# TPSM84824MOL.net
KiCad netlist of a schematic drawn in Altium Designer
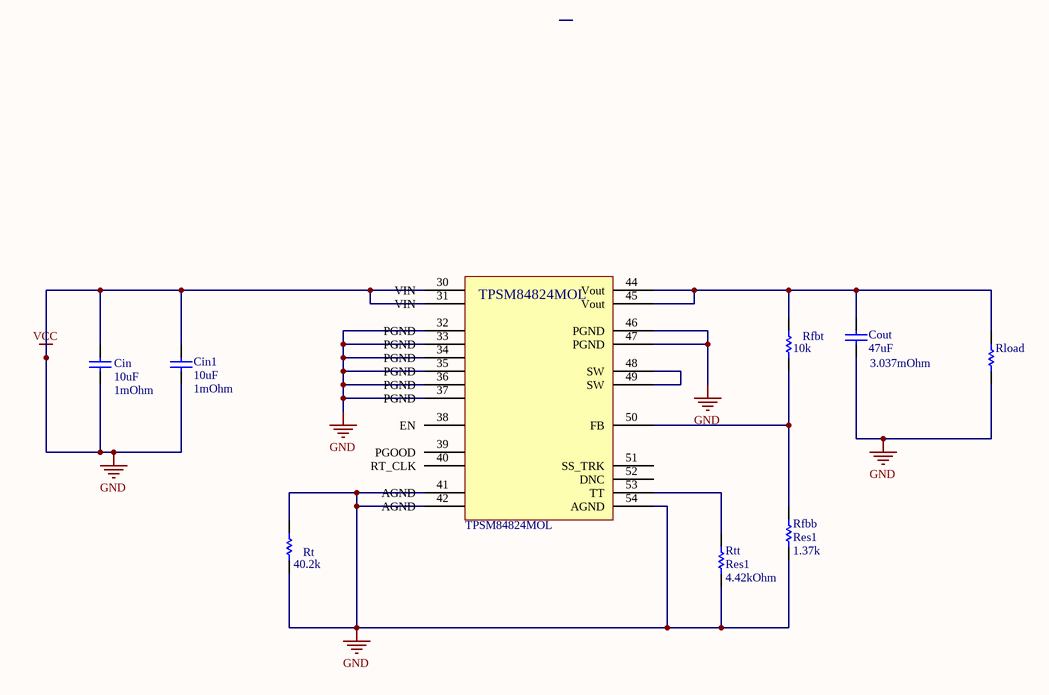
[diagram p0: TPSM84824MOL.SchDoc]

(export (version "E")
  (design (tool "Eeschema 10.0.6"))
  (components
    (comp (ref "Cin")
      (value "10uF")
      (footprint "RAD-0.3")
      (description "Capacitor")
      (fields
        (field (name "ALTIUM_UNNAMED_1") "1mOhm")
        (field (name "Comment") "Cap")
        (field (name "PUBLISHER") "Altium Limited")
      )
      (libsource (lib "Miscellaneous Devices") (part "Cap"))
    )
    (comp (ref "Cin1")
      (value "10uF")
      (footprint "RAD-0.3")
      (description "Capacitor")
      (fields
        (field (name "ALTIUM_UNNAMED_1") "1mOhm")
        (field (name "Comment") "Cap")
        (field (name "PUBLISHER") "Altium Limited")
      )
      (libsource (lib "Miscellaneous Devices") (part "Cap"))
    )
    (comp (ref "Cout")
      (value "47uF")
      (footprint "RAD-0.3")
      (description "Capacitor")
      (fields
        (field (name "RES") "3.037mOhm")
        (field (name "Comment") "Cap")
        (field (name "PUBLISHER") "Altium Limited")
      )
      (libsource (lib "Miscellaneous Devices") (part "Cap"))
    )
    (comp (ref "Rfbb")
      (value "Res1")
      (footprint "AXIAL-0.3")
      (description "Resistor")
      (fields (field (name "ALTIUM_VALUE") "1.37k") (field (name "PUBLISHER") "Altium Limited"))
      (libsource (lib "Miscellaneous Devices") (part "Res1"))
    )
    (comp (ref "Rfbt")
      (value "10k")
      (footprint "AXIAL-0.3")
      (description "Resistor")
      (fields (field (name "Comment") "Res1") (field (name "PUBLISHER") "Altium Limited"))
      (libsource (lib "Miscellaneous Devices") (part "Res1"))
    )
    (comp (ref "Rload")
      (value "Res1")
      (footprint "AXIAL-0.3")
      (description "Resistor")
      (fields (field (name "PUBLISHER") "Altium Limited"))
      (libsource (lib "Miscellaneous Devices") (part "Res1"))
    )
    (comp (ref "Rt")
      (value "40.2k")
      (footprint "AXIAL-0.3")
      (description "Resistor")
      (fields (field (name "Comment") "Res1") (field (name "PUBLISHER") "Altium Limited"))
      (libsource (lib "Miscellaneous Devices") (part "Res1"))
    )
    (comp (ref "Rtt")
      (value "Res1")
      (footprint "AXIAL-0.3")
      (description "Resistor")
      (fields (field (name "ALTIUM_VALUE") "4.42kOhm") (field (name "PUBLISHER") "Altium Limited"))
      (libsource (lib "Miscellaneous Devices") (part "Res1"))
    )
    (comp (ref "TPSM84824MOL") (value "TPSM84824MOL") (libsource (lib "TPSM84824MOL") (part "TPSM84824MOL")))
  )
  (nets
    (net (code "1") (name "GND") (class "Default")
      (node (ref "Cin") (pin "1") (pinfunction "1_1") (pintype "passive"))
      (node (ref "Cin") (pin "2") (pinfunction "2_2") (pintype "passive"))
      (node (ref "Cin1") (pin "1") (pinfunction "1_1") (pintype "passive"))
      (node (ref "Cin1") (pin "2") (pinfunction "2_2") (pintype "passive"))
      (node (ref "Cout") (pin "1") (pinfunction "1_1") (pintype "passive"))
      (node (ref "Rfbb") (pin "1") (pinfunction "1_1") (pintype "passive"))
      (node (ref "Rload") (pin "1") (pinfunction "1_1") (pintype "passive"))
      (node (ref "Rt") (pin "1") (pinfunction "1_1") (pintype "passive"))
      (node (ref "Rt") (pin "2") (pinfunction "2_2") (pintype "passive"))
      (node (ref "Rtt") (pin "1") (pinfunction "1_1") (pintype "passive"))
      (node (ref "TPSM84824MOL") (pin "46") (pinfunction "PGND_46") (pintype "passive"))
      (node (ref "TPSM84824MOL") (pin "47") (pinfunction "PGND_47") (pintype "passive"))
      (node (ref "TPSM84824MOL") (pin "54") (pinfunction "AGND_54") (pintype "passive"))
    )
    (net (code "2") (name "Net-(Cout-Pad2)") (class "Default")
      (node (ref "Cout") (pin "2") (pinfunction "2_2") (pintype "passive"))
      (node (ref "Rfbt") (pin "2") (pinfunction "2_2") (pintype "passive"))
      (node (ref "Rload") (pin "2") (pinfunction "2_2") (pintype "passive"))
      (node (ref "TPSM84824MOL") (pin "44") (pinfunction "Vout_44") (pintype "passive"))
      (node (ref "TPSM84824MOL") (pin "45") (pinfunction "Vout_45") (pintype "passive"))
    )
    (net (code "3") (name "Net-(TPSM84824MOL-FB)") (class "Default")
      (node (ref "Rfbb") (pin "2") (pinfunction "2_2") (pintype "passive"))
      (node (ref "Rfbt") (pin "1") (pinfunction "1_1") (pintype "passive"))
      (node (ref "TPSM84824MOL") (pin "50") (pinfunction "FB_50") (pintype "passive"))
    )
    (net (code "4") (name "Net-(TPSM84824MOL-SW-Pad48)") (class "Default")
      (node (ref "TPSM84824MOL") (pin "48") (pinfunction "SW_48") (pintype "passive"))
      (node (ref "TPSM84824MOL") (pin "49") (pinfunction "SW_49") (pintype "passive"))
    )
    (net (code "5") (name "Net-(TPSM84824MOL-TT)") (class "Default")
      (node (ref "Rtt") (pin "2") (pinfunction "2_2") (pintype "passive"))
      (node (ref "TPSM84824MOL") (pin "53") (pinfunction "TT_53") (pintype "passive"))
    )
    (net (code "6") (name "unconnected-(TPSM84824MOL-AGND-Pad41)") (class "Default")
      (node (ref "TPSM84824MOL") (pin "41") (pinfunction "AGND_41") (pintype "passive"))
    )
    (net (code "7") (name "unconnected-(TPSM84824MOL-AGND-Pad42)") (class "Default")
      (node (ref "TPSM84824MOL") (pin "42") (pinfunction "AGND_42") (pintype "passive"))
    )
    (net (code "8") (name "unconnected-(TPSM84824MOL-DNC-Pad52)") (class "Default")
      (node (ref "TPSM84824MOL") (pin "52") (pinfunction "DNC_52") (pintype "passive"))
    )
    (net (code "9") (name "unconnected-(TPSM84824MOL-EN-Pad38)") (class "Default")
      (node (ref "TPSM84824MOL") (pin "38") (pinfunction "EN_38") (pintype "passive"))
    )
    (net (code "10") (name "unconnected-(TPSM84824MOL-PGND-Pad32)") (class "Default")
      (node (ref "TPSM84824MOL") (pin "32") (pinfunction "PGND_32") (pintype "passive"))
    )
    (net (code "11") (name "unconnected-(TPSM84824MOL-PGND-Pad33)") (class "Default")
      (node (ref "TPSM84824MOL") (pin "33") (pinfunction "PGND_33") (pintype "passive"))
    )
    (net (code "12") (name "unconnected-(TPSM84824MOL-PGND-Pad34)") (class "Default")
      (node (ref "TPSM84824MOL") (pin "34") (pinfunction "PGND_34") (pintype "passive"))
    )
    (net (code "13") (name "unconnected-(TPSM84824MOL-PGND-Pad35)") (class "Default")
      (node (ref "TPSM84824MOL") (pin "35") (pinfunction "PGND_35") (pintype "passive"))
    )
    (net (code "14") (name "unconnected-(TPSM84824MOL-PGND-Pad36)") (class "Default")
      (node (ref "TPSM84824MOL") (pin "36") (pinfunction "PGND_36") (pintype "passive"))
    )
    (net (code "15") (name "unconnected-(TPSM84824MOL-PGND-Pad37)") (class "Default")
      (node (ref "TPSM84824MOL") (pin "37") (pinfunction "PGND_37") (pintype "passive"))
    )
    (net (code "16") (name "unconnected-(TPSM84824MOL-PGOOD-Pad39)") (class "Default")
      (node (ref "TPSM84824MOL") (pin "39") (pinfunction "PGOOD_39") (pintype "passive"))
    )
    (net (code "17") (name "unconnected-(TPSM84824MOL-RT_CLK-Pad40)") (class "Default")
      (node (ref "TPSM84824MOL") (pin "40") (pinfunction "RT_CLK_40") (pintype "passive"))
    )
    (net (code "18") (name "unconnected-(TPSM84824MOL-SS_TRK-Pad51)") (class "Default")
      (node (ref "TPSM84824MOL") (pin "51") (pinfunction "SS_TRK_51") (pintype "passive"))
    )
    (net (code "19") (name "unconnected-(TPSM84824MOL-VIN-Pad30)") (class "Default")
      (node (ref "TPSM84824MOL") (pin "30") (pinfunction "VIN_30") (pintype "passive"))
    )
    (net (code "20") (name "unconnected-(TPSM84824MOL-VIN-Pad31)") (class "Default")
      (node (ref "TPSM84824MOL") (pin "31") (pinfunction "VIN_31") (pintype "passive"))
    )
  )
)
